# schematic.net
KiCad netlist of a schematic drawn in EAGLE
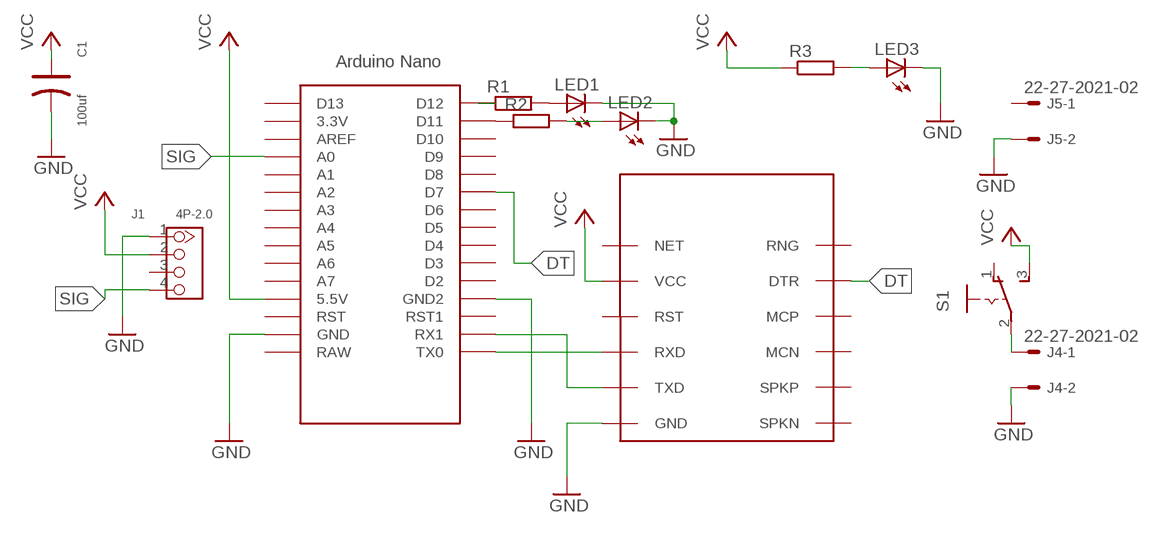
[diagram p0: schematic, sheet 1]

(export (version "E")
  (design (tool "Eeschema 10.0.6"))
  (components
    (comp (ref "C1")
      (value "100uf")
      (footprint "eagle-import:PC-D5.3MM")
      (fields (field (name "MPN") "KS 100uF/16V"))
      (libsource (lib "eagle-import") (part "DIP-ALUMINUM-100UF-16V(D5-H7MM)"))
    )
    (comp (ref "J1")
      (value "4P-2.0")
      (footprint "eagle-import:HW4-2.0")
      (libsource (lib "eagle-import") (part "GROVE-CONNECTOR-DIP(4P-2.0)"))
    )
    (comp (ref "J4")
      (value "22-27-2021-02")
      (footprint "eagle-import:6410-02")
      (fields (field (name "MF") "MOLEX"))
      (libsource (lib "eagle-import") (part "22-?-0227-2021"))
    )
    (comp (ref "J5")
      (value "22-27-2021-02")
      (footprint "eagle-import:6410-02")
      (fields (field (name "MF") "MOLEX"))
      (libsource (lib "eagle-import") (part "22-?-0227-2021"))
    )
    (comp (ref "LED1")
      (value "LED5MM")
      (footprint "eagle-import:LED5MM")
      (libsource (lib "eagle-import") (part "LED5MM"))
    )
    (comp (ref "LED2")
      (value "LED5MM")
      (footprint "eagle-import:LED5MM")
      (libsource (lib "eagle-import") (part "LED5MM"))
    )
    (comp (ref "LED3")
      (value "LED5MM")
      (footprint "eagle-import:LED5MM")
      (libsource (lib "eagle-import") (part "LED5MM"))
    )
    (comp (ref "R1")
      (value "R-EU_0204/7")
      (footprint "eagle-import:0204_7")
      (libsource (lib "eagle-import") (part "R-EU_0204/7"))
    )
    (comp (ref "R2")
      (value "R-EU_0204/7")
      (footprint "eagle-import:0204_7")
      (libsource (lib "eagle-import") (part "R-EU_0204/7"))
    )
    (comp (ref "R3")
      (value "R-EU_0204/7")
      (footprint "eagle-import:0204_7")
      (libsource (lib "eagle-import") (part "R-EU_0204/7"))
    )
    (comp (ref "S1")
      (value "M251")
      (footprint "eagle-import:M251")
      (libsource (lib "eagle-import") (part "M251"))
    )
    (comp (ref "U$1")
      (value "NANO")
      (footprint "eagle-import:NANO")
      (libsource (lib "eagle-import") (part "NANO"))
    )
    (comp (ref "U$2")
      (value "SIM800L")
      (footprint "eagle-import:SIM-CORE")
      (libsource (lib "eagle-import") (part "SIM800L"))
    )
  )
  (nets
    (net (code "1") (name "DT") (class "Default")
      (node (ref "U$1") (pin "D7") (pinfunction "D7_D7") (pintype "bidirectional"))
      (node (ref "U$2") (pin "DTR") (pinfunction "DTR_DTR") (pintype "bidirectional"))
    )
    (net (code "2") (name "GND") (class "Default")
      (node (ref "C1") (pin "-") (pinfunction "-_-") (pintype "passive"))
      (node (ref "J1") (pin "1") (pinfunction "1_1") (pintype "bidirectional"))
      (node (ref "J4") (pin "2") (pinfunction "S_2") (pintype "passive"))
      (node (ref "J5") (pin "2") (pinfunction "S_2") (pintype "passive"))
      (node (ref "LED1") (pin "K") (pinfunction "C_K") (pintype "passive"))
      (node (ref "LED2") (pin "K") (pinfunction "C_K") (pintype "passive"))
      (node (ref "LED3") (pin "K") (pinfunction "C_K") (pintype "passive"))
      (node (ref "U$1") (pin "GND") (pinfunction "GND_GND") (pintype "bidirectional"))
      (node (ref "U$1") (pin "GND1") (pinfunction "GND2_GND1") (pintype "bidirectional"))
      (node (ref "U$2") (pin "GND") (pinfunction "GND_GND") (pintype "bidirectional"))
    )
    (net (code "3") (name "Net-(J4A-S)") (class "Default")
      (node (ref "J4") (pin "1") (pinfunction "S_1") (pintype "passive"))
      (node (ref "S1") (pin "2") (pinfunction "P_2") (pintype "passive"))
    )
    (net (code "4") (name "Net-(LED1-PadA)") (class "Default")
      (node (ref "LED1") (pin "A") (pinfunction "A_A") (pintype "passive"))
      (node (ref "R1") (pin "2") (pinfunction "2_2") (pintype "passive"))
    )
    (net (code "5") (name "Net-(LED2-PadA)") (class "Default")
      (node (ref "LED2") (pin "A") (pinfunction "A_A") (pintype "passive"))
      (node (ref "R2") (pin "2") (pinfunction "2_2") (pintype "passive"))
    )
    (net (code "6") (name "Net-(LED3-PadA)") (class "Default")
      (node (ref "LED3") (pin "A") (pinfunction "A_A") (pintype "passive"))
      (node (ref "R3") (pin "2") (pinfunction "2_2") (pintype "passive"))
    )
    (net (code "7") (name "Net-(R1-Pad1)") (class "Default")
      (node (ref "R1") (pin "1") (pinfunction "1_1") (pintype "passive"))
      (node (ref "U$1") (pin "D12") (pinfunction "D12_D12") (pintype "bidirectional"))
    )
    (net (code "8") (name "Net-(R2-Pad1)") (class "Default")
      (node (ref "R2") (pin "1") (pinfunction "1_1") (pintype "passive"))
      (node (ref "U$1") (pin "D11") (pinfunction "D11_D11") (pintype "bidirectional"))
    )
    (net (code "9") (name "Net-(U$1-PadRX1)") (class "Default")
      (node (ref "U$1") (pin "RX1") (pinfunction "RX1_RX1") (pintype "bidirectional"))
      (node (ref "U$2") (pin "TXD") (pinfunction "TXD_TXD") (pintype "bidirectional"))
    )
    (net (code "10") (name "Net-(U$1-PadTX0)") (class "Default")
      (node (ref "U$1") (pin "TX0") (pinfunction "TX0_TX0") (pintype "bidirectional"))
      (node (ref "U$2") (pin "RXD") (pinfunction "RXD_RXD") (pintype "bidirectional"))
    )
    (net (code "11") (name "SIG") (class "Default")
      (node (ref "J1") (pin "4") (pinfunction "4_4") (pintype "bidirectional"))
      (node (ref "U$1") (pin "A0") (pinfunction "A0_A0") (pintype "bidirectional"))
    )
    (net (code "12") (name "VCC") (class "Default")
      (node (ref "C1") (pin "+") (pinfunction "+_+") (pintype "passive"))
      (node (ref "J1") (pin "2") (pinfunction "2_2") (pintype "bidirectional"))
      (node (ref "R3") (pin "1") (pinfunction "1_1") (pintype "passive"))
      (node (ref "S1") (pin "3") (pinfunction "S_3") (pintype "passive"))
      (node (ref "U$1") (pin "5V") (pinfunction "5.5V_5V") (pintype "bidirectional"))
      (node (ref "U$2") (pin "VCC") (pinfunction "VCC_VCC") (pintype "bidirectional"))
    )
    (net (code "13") (name "unconnected-(J1-Pad3)") (class "Default")
      (node (ref "J1") (pin "3") (pinfunction "3_3") (pintype "bidirectional"))
    )
    (net (code "14") (name "unconnected-(J5A-S-Pad1)") (class "Default")
      (node (ref "J5") (pin "1") (pinfunction "S_1") (pintype "passive"))
    )
    (net (code "15") (name "unconnected-(S1-O-Pad1)") (class "Default")
      (node (ref "S1") (pin "1") (pinfunction "O_1") (pintype "passive"))
    )
    (net (code "16") (name "unconnected-(U$1-Pad3.3V)") (class "Default")
      (node (ref "U$1") (pin "3.3V") (pinfunction "3.3V_3.3V") (pintype "bidirectional"))
    )
    (net (code "17") (name "unconnected-(U$1-PadA1)") (class "Default")
      (node (ref "U$1") (pin "A1") (pinfunction "A1_A1") (pintype "bidirectional"))
    )
    (net (code "18") (name "unconnected-(U$1-PadA2)") (class "Default")
      (node (ref "U$1") (pin "A2") (pinfunction "A2_A2") (pintype "bidirectional"))
    )
    (net (code "19") (name "unconnected-(U$1-PadA3)") (class "Default")
      (node (ref "U$1") (pin "A3") (pinfunction "A3_A3") (pintype "bidirectional"))
    )
    (net (code "20") (name "unconnected-(U$1-PadA4)") (class "Default")
      (node (ref "U$1") (pin "A4") (pinfunction "A4_A4") (pintype "bidirectional"))
    )
    (net (code "21") (name "unconnected-(U$1-PadA5)") (class "Default")
      (node (ref "U$1") (pin "A5") (pinfunction "A5_A5") (pintype "bidirectional"))
    )
    (net (code "22") (name "unconnected-(U$1-PadA6)") (class "Default")
      (node (ref "U$1") (pin "A6") (pinfunction "A6_A6") (pintype "bidirectional"))
    )
    (net (code "23") (name "unconnected-(U$1-PadA7)") (class "Default")
      (node (ref "U$1") (pin "A7") (pinfunction "A7_A7") (pintype "bidirectional"))
    )
    (net (code "24") (name "unconnected-(U$1-PadAREF)") (class "Default")
      (node (ref "U$1") (pin "AREF") (pinfunction "AREF_AREF") (pintype "bidirectional"))
    )
    (net (code "25") (name "unconnected-(U$1-PadD2)") (class "Default")
      (node (ref "U$1") (pin "D2") (pinfunction "D2_D2") (pintype "bidirectional"))
    )
    (net (code "26") (name "unconnected-(U$1-PadD3)") (class "Default")
      (node (ref "U$1") (pin "D3") (pinfunction "D3_D3") (pintype "bidirectional"))
    )
    (net (code "27") (name "unconnected-(U$1-PadD4)") (class "Default")
      (node (ref "U$1") (pin "D4") (pinfunction "D4_D4") (pintype "bidirectional"))
    )
    (net (code "28") (name "unconnected-(U$1-PadD5)") (class "Default")
      (node (ref "U$1") (pin "D5") (pinfunction "D5_D5") (pintype "bidirectional"))
    )
    (net (code "29") (name "unconnected-(U$1-PadD6)") (class "Default")
      (node (ref "U$1") (pin "D6") (pinfunction "D6_D6") (pintype "bidirectional"))
    )
    (net (code "30") (name "unconnected-(U$1-PadD8)") (class "Default")
      (node (ref "U$1") (pin "D8") (pinfunction "D8_D8") (pintype "bidirectional"))
    )
    (net (code "31") (name "unconnected-(U$1-PadD9)") (class "Default")
      (node (ref "U$1") (pin "D9") (pinfunction "D9_D9") (pintype "bidirectional"))
    )
    (net (code "32") (name "unconnected-(U$1-PadD10)") (class "Default")
      (node (ref "U$1") (pin "D10") (pinfunction "D10_D10") (pintype "bidirectional"))
    )
    (net (code "33") (name "unconnected-(U$1-PadD13)") (class "Default")
      (node (ref "U$1") (pin "D13") (pinfunction "D13_D13") (pintype "bidirectional"))
    )
    (net (code "34") (name "unconnected-(U$1-PadICSP1)") (class "Default")
      (node (ref "U$1") (pin "ICSP1") (pinfunction "ICSP1_ICSP1") (pintype "bidirectional"))
    )
    (net (code "35") (name "unconnected-(U$1-PadICSP2)") (class "Default")
      (node (ref "U$1") (pin "ICSP2") (pinfunction "ICSP2_ICSP2") (pintype "bidirectional"))
    )
    (net (code "36") (name "unconnected-(U$1-PadICSP3)") (class "Default")
      (node (ref "U$1") (pin "ICSP3") (pinfunction "ICSP3_ICSP3") (pintype "bidirectional"))
    )
    (net (code "37") (name "unconnected-(U$1-PadICSP4)") (class "Default")
      (node (ref "U$1") (pin "ICSP4") (pinfunction "ICSP4_ICSP4") (pintype "bidirectional"))
    )
    (net (code "38") (name "unconnected-(U$1-PadICSP5)") (class "Default")
      (node (ref "U$1") (pin "ICSP5") (pinfunction "ICSP5_ICSP5") (pintype "bidirectional"))
    )
    (net (code "39") (name "unconnected-(U$1-PadICSP6)") (class "Default")
      (node (ref "U$1") (pin "ICSP6") (pinfunction "ICSP6_ICSP6") (pintype "bidirectional"))
    )
    (net (code "40") (name "unconnected-(U$1-PadRAW)") (class "Default")
      (node (ref "U$1") (pin "RAW") (pinfunction "RAW_RAW") (pintype "bidirectional"))
    )
    (net (code "41") (name "unconnected-(U$1-PadRST)") (class "Default")
      (node (ref "U$1") (pin "RST") (pinfunction "RST_RST") (pintype "bidirectional"))
    )
    (net (code "42") (name "unconnected-(U$1-PadRST1)") (class "Default")
      (node (ref "U$1") (pin "RST1") (pinfunction "RST1_RST1") (pintype "bidirectional"))
    )
    (net (code "43") (name "unconnected-(U$2-PadMCN)") (class "Default")
      (node (ref "U$2") (pin "MCN") (pinfunction "MCN_MCN") (pintype "bidirectional"))
    )
    (net (code "44") (name "unconnected-(U$2-PadMCP)") (class "Default")
      (node (ref "U$2") (pin "MCP") (pinfunction "MCP_MCP") (pintype "bidirectional"))
    )
    (net (code "45") (name "unconnected-(U$2-PadNET)") (class "Default")
      (node (ref "U$2") (pin "NET") (pinfunction "NET_NET") (pintype "bidirectional"))
    )
    (net (code "46") (name "unconnected-(U$2-PadRNG)") (class "Default")
      (node (ref "U$2") (pin "RNG") (pinfunction "RNG_RNG") (pintype "bidirectional"))
    )
    (net (code "47") (name "unconnected-(U$2-PadRST)") (class "Default")
      (node (ref "U$2") (pin "RST") (pinfunction "RST_RST") (pintype "bidirectional"))
    )
    (net (code "48") (name "unconnected-(U$2-PadSPKN)") (class "Default")
      (node (ref "U$2") (pin "SPKN") (pinfunction "SPKN_SPKN") (pintype "bidirectional"))
    )
    (net (code "49") (name "unconnected-(U$2-PadSPKP)") (class "Default")
      (node (ref "U$2") (pin "SPKP") (pinfunction "SPKP_SPKP") (pintype "bidirectional"))
    )
  )
)
